# EasyEDAProject.net
KiCad netlist of a schematic drawn in EasyEDA Pro
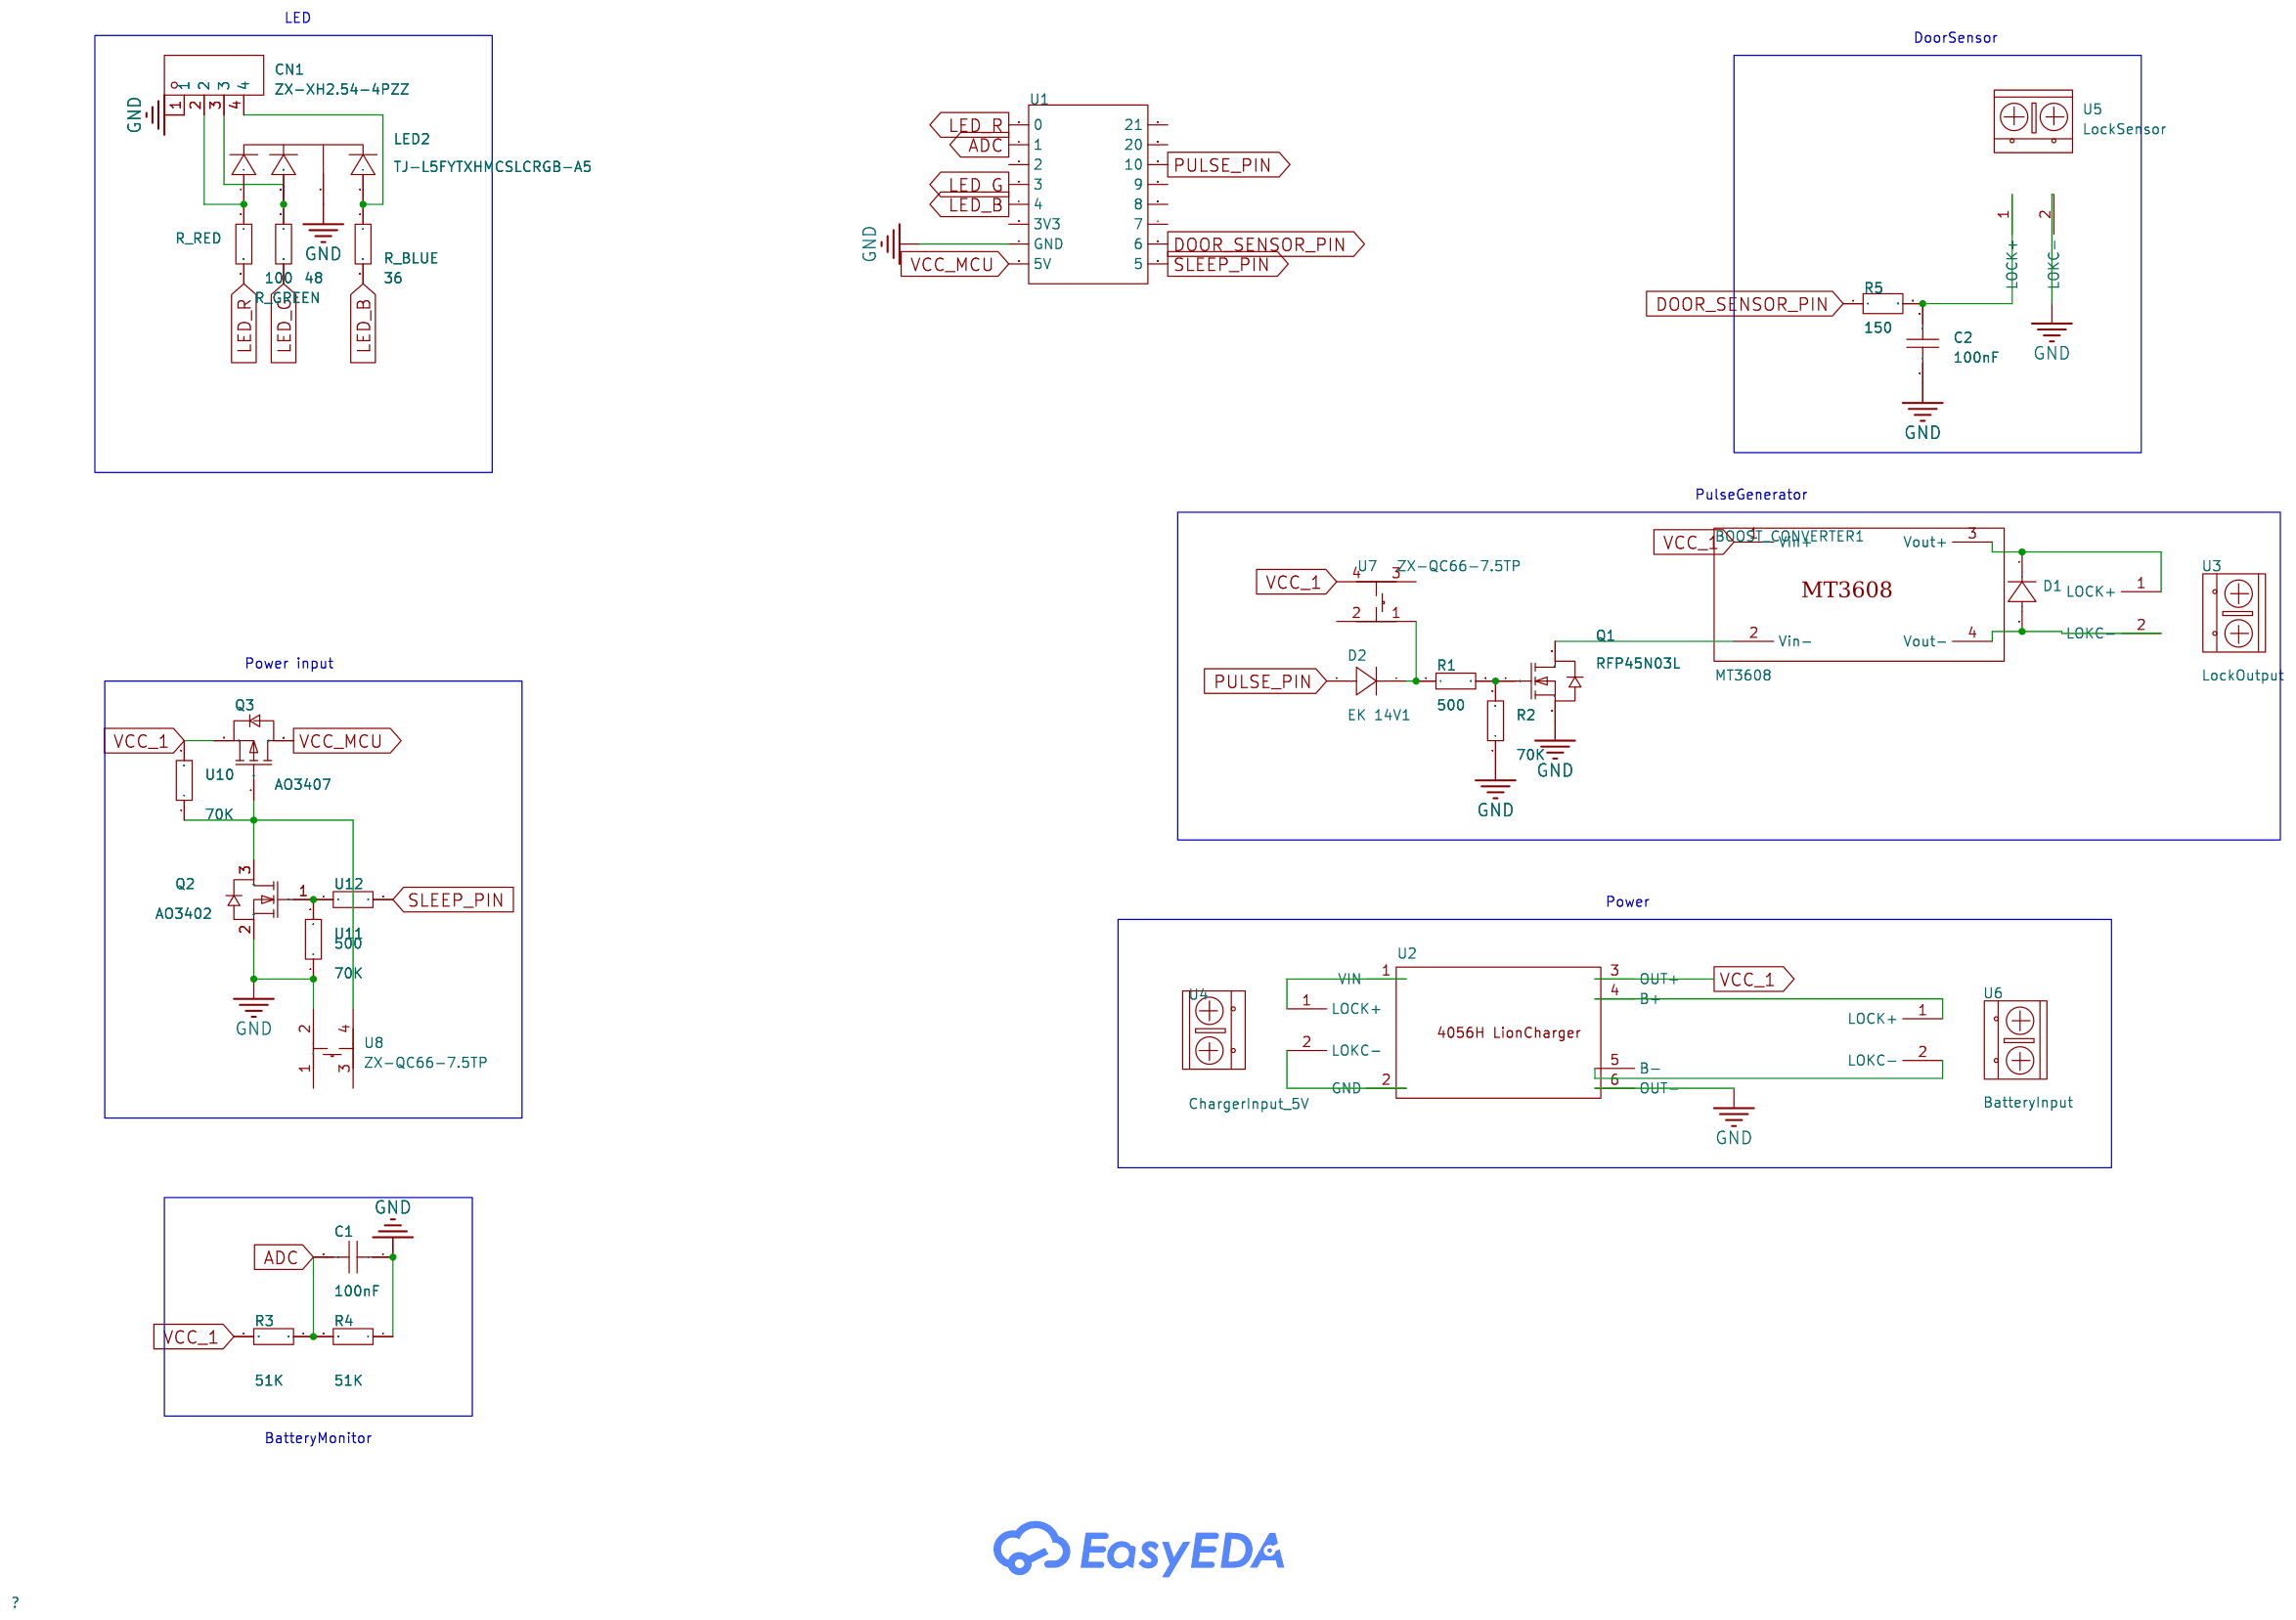
[diagram p0: schematic sheet]

(export (version "E")
  (design (tool "Eeschema 10.0.6"))
  (components
    (comp (ref "BOOST_CONVERTER1")
      (value "MT3608")
      (footprint "easyedapro:MT3608 BOOST")
      (libsource (lib "easyedapro") (part "MT3608"))
    )
    (comp (ref "C1")
      (value "100nF")
      (footprint "easyedapro:C0603")
      (libsource (lib "easyedapro") (part "CAP"))
    )
    (comp (ref "C2")
      (value "100nF")
      (footprint "easyedapro:CAP-TH_L5.0-W2.5-P5.00-D1.0")
      (fields
        (field (name "Manufacturer Part") "CC1H104MC1FD3F6C10MF")
        (field (name "Manufacturer") "Dersonic(德尔创)")
      )
      (libsource (lib "easyedapro") (part "CC1H104MC1FD3F6C10MF"))
    )
    (comp (ref "CN1")
      (value "ZX-XH2.54-4PZZ")
      (footprint "easyedapro:CONN-TH_4P-P2.50_4PIN")
      (fields (field (name "Manufacturer") "Megastar(兆星)"))
      (libsource (lib "easyedapro") (part "ZX-XH2.54-4PZZ"))
    )
    (comp (ref "D1")
      (value "~")
      (footprint "easyedapro:SMA_L4.4-W2.8-LS5.4-RD")
      (libsource (lib "easyedapro") (part "D_1N4007"))
    )
    (comp (ref "D2")
      (value "EK 14V1")
      (footprint "easyedapro:SMA_L4.4-W2.8-LS5.4-RD")
      (fields (field (name "Manufacturer") "SANKEN(三垦)"))
      (libsource (lib "easyedapro") (part "D_1N4007"))
    )
    (comp (ref "LED2")
      (value "TJ-L5FYTXHMCSLCRGB-A5")
      (footprint "easyedapro:LED-TH_4P-BD5.8-P1.30")
      (fields (field (name "Manufacturer") "TOGIALED(统佳)"))
      (libsource (lib "easyedapro") (part "TJ-L5FYTXHMCSLCRGB-A5"))
    )
    (comp (ref "Q1")
      (value "RFP45N03L")
      (footprint "easyedapro:TO-220-3_L9.9-W4.5-P2.54-L")
      (fields (field (name "Manufacturer") "HARRIS(哈利斯)"))
      (libsource (lib "easyedapro") (part "RFP45N03L"))
    )
    (comp (ref "Q2")
      (value "AO3402")
      (footprint "easyedapro:SOT-23_L2.9-W1.3-P1.90-LS2.4-BR")
      (fields (field (name "Manufacturer") "GOODWORK(固得沃克)"))
      (libsource (lib "easyedapro") (part "AO3402_C2938369"))
    )
    (comp (ref "Q3")
      (value "AO3407")
      (footprint "easyedapro:SOT-23-3_L2.9-W1.3-P1.90-LS2.4-BR")
      (fields (field (name "Manufacturer") "YONGYUTAI(永裕泰)"))
      (libsource (lib "easyedapro") (part "AO3407_C6562206"))
    )
    (comp (ref "R1")
      (value "500")
      (footprint "easyedapro:R_AXIAL-0.5")
      (libsource (lib "easyedapro") (part "Res"))
    )
    (comp (ref "R2")
      (value "70K")
      (footprint "easyedapro:R_AXIAL-0.5")
      (libsource (lib "easyedapro") (part "Res"))
    )
    (comp (ref "R3")
      (value "51K")
      (footprint "easyedapro:R_AXIAL-0.5")
      (libsource (lib "easyedapro") (part "Res"))
    )
    (comp (ref "R4")
      (value "51K")
      (footprint "easyedapro:R_AXIAL-0.5")
      (libsource (lib "easyedapro") (part "Res"))
    )
    (comp (ref "R5")
      (value "150")
      (footprint "easyedapro:RES-TH_BD2.3-L6.5-P10.50-D0.5")
      (fields (field (name "Manufacturer Part") "MF1/4W-1KΩ±1%T52") (field (name "Manufacturer") "华星机电"))
      (libsource (lib "easyedapro") (part "MF1/4W-1KΩ±1%T52"))
    )
    (comp (ref "R_BLUE")
      (value "36")
      (footprint "easyedapro:R_AXIAL-0.5")
      (libsource (lib "easyedapro") (part "Res"))
    )
    (comp (ref "R_GREEN")
      (value "48")
      (footprint "easyedapro:R_AXIAL-0.5")
      (libsource (lib "easyedapro") (part "Res"))
    )
    (comp (ref "R_RED")
      (value "100")
      (footprint "easyedapro:R_AXIAL-0.5")
      (libsource (lib "easyedapro") (part "Res"))
    )
    (comp (ref "U1")
      (value "~")
      (footprint "easyedapro:ESP32-C3 SuperMini")
      (libsource (lib "easyedapro") (part "ESP32-C3 SuperMini"))
    )
    (comp (ref "U2")
      (value "~")
      (footprint "easyedapro:LionCharger")
      (libsource (lib "easyedapro") (part "Lio-Charger"))
    )
    (comp (ref "U3")
      (value "LockOutput")
      (footprint "easyedapro:TerminalBlock:TerminalBlock_bornier-2_P5.08mm")
      (libsource (lib "easyedapro") (part "2pin Terminal"))
    )
    (comp (ref "U4")
      (value "ChargerInput_5V")
      (footprint "easyedapro:TerminalBlock:TerminalBlock_bornier-2_P5.08mm")
      (libsource (lib "easyedapro") (part "2pin Terminal"))
    )
    (comp (ref "U5")
      (value "LockSensor")
      (footprint "easyedapro:TerminalBlock:TerminalBlock_bornier-2_P5.08mm")
      (libsource (lib "easyedapro") (part "2pin Terminal"))
    )
    (comp (ref "U6")
      (value "BatteryInput")
      (footprint "easyedapro:TerminalBlock:TerminalBlock_bornier-2_P5.08mm")
      (libsource (lib "easyedapro") (part "2pin Terminal"))
    )
    (comp (ref "U7")
      (value "ZX-QC66-7.5TP")
      (footprint "easyedapro:KEY-SMD_4P-L6.0-W6.0-P4.50-LS8.6")
      (fields (field (name "Manufacturer") "Megastar(兆星)"))
      (libsource (lib "easyedapro") (part "ZX-QC66-7.5TP"))
    )
    (comp (ref "U8")
      (value "ZX-QC66-7.5TP")
      (footprint "easyedapro:KEY-SMD_4P-L6.0-W6.0-P4.50-LS8.6")
      (fields (field (name "Manufacturer") "Megastar(兆星)"))
      (libsource (lib "easyedapro") (part "ZX-QC66-7.5TP"))
    )
    (comp (ref "U10")
      (value "70K")
      (footprint "easyedapro:R_AXIAL-0.5")
      (libsource (lib "easyedapro") (part "Res"))
    )
    (comp (ref "U11")
      (value "70K")
      (footprint "easyedapro:R_AXIAL-0.5")
      (libsource (lib "easyedapro") (part "Res"))
    )
    (comp (ref "U12")
      (value "500")
      (footprint "easyedapro:R_AXIAL-0.5")
      (libsource (lib "easyedapro") (part "Res"))
    )
  )
  (nets
    (net (code "1") (name "ADC") (class "Default")
      (node (ref "C1") (pin "2") (pinfunction "2_2") (pintype "input"))
      (node (ref "R3") (pin "1") (pinfunction "1_1") (pintype "input"))
      (node (ref "R4") (pin "2") (pinfunction "2_2") (pintype "input"))
      (node (ref "U1") (pin "1") (pinfunction "1_1") (pintype "input"))
    )
    (net (code "2") (name "DOOR_SENSOR_PIN") (class "Default")
      (node (ref "R5") (pin "1") (pinfunction "1_1") (pintype "unspecified"))
      (node (ref "U1") (pin "6") (pinfunction "6_6") (pintype "input"))
    )
    (net (code "3") (name "GND") (class "Default")
      (node (ref "C1") (pin "1") (pinfunction "1_1") (pintype "input"))
      (node (ref "C2") (pin "1") (pinfunction "1_1") (pintype "unspecified"))
      (node (ref "CN1") (pin "1") (pinfunction "1_1") (pintype "unspecified"))
      (node (ref "LED2") (pin "2") (pinfunction "-_2") (pintype "unspecified"))
      (node (ref "Q1") (pin "3") (pinfunction "S_3") (pintype "unspecified"))
      (node (ref "Q2") (pin "2") (pinfunction "S_2") (pintype "unspecified"))
      (node (ref "R2") (pin "1") (pinfunction "1_1") (pintype "input"))
      (node (ref "R4") (pin "1") (pinfunction "1_1") (pintype "input"))
      (node (ref "U1") (pin "14") (pinfunction "GND_14") (pintype "input"))
      (node (ref "U11") (pin "1") (pinfunction "1_1") (pintype "input"))
      (node (ref "U2") (pin "6") (pinfunction "OUT-_6") (pintype "output"))
      (node (ref "U5") (pin "2") (pinfunction "LOKC-_2") (pintype "input"))
      (node (ref "U8") (pin "2") (pinfunction "2_2") (pintype "unspecified"))
    )
    (net (code "4") (name "LED_B") (class "Default")
      (node (ref "R_BLUE") (pin "2") (pinfunction "2_2") (pintype "input"))
      (node (ref "U1") (pin "4") (pinfunction "4_4") (pintype "input"))
    )
    (net (code "5") (name "LED_G") (class "Default")
      (node (ref "R_GREEN") (pin "2") (pinfunction "2_2") (pintype "input"))
      (node (ref "U1") (pin "3") (pinfunction "3_3") (pintype "input"))
    )
    (net (code "6") (name "LED_R") (class "Default")
      (node (ref "R_RED") (pin "2") (pinfunction "2_2") (pintype "input"))
      (node (ref "U1") (pin "0") (pinfunction "0_0") (pintype "input"))
    )
    (net (code "7") (name "Net-(BOOST_CONVERTER1-Vin-)") (class "Default")
      (node (ref "BOOST_CONVERTER1") (pin "2") (pinfunction "Vin-_2") (pintype "input"))
      (node (ref "Q1") (pin "2") (pinfunction "D_2") (pintype "unspecified"))
    )
    (net (code "8") (name "Net-(BOOST_CONVERTER1-Vout+)") (class "Default")
      (node (ref "BOOST_CONVERTER1") (pin "3") (pinfunction "Vout+_3") (pintype "input"))
      (node (ref "D1") (pin "1") (pinfunction "K_1") (pintype "input"))
      (node (ref "U3") (pin "1") (pinfunction "LOCK+_1") (pintype "input"))
    )
    (net (code "9") (name "Net-(BOOST_CONVERTER1-Vout-)") (class "Default")
      (node (ref "BOOST_CONVERTER1") (pin "4") (pinfunction "Vout-_4") (pintype "input"))
      (node (ref "D1") (pin "2") (pinfunction "A_2") (pintype "input"))
      (node (ref "U3") (pin "2") (pinfunction "LOKC-_2") (pintype "input"))
    )
    (net (code "10") (name "Net-(CN1-Pad2)") (class "Default")
      (node (ref "CN1") (pin "2") (pinfunction "2_2") (pintype "unspecified"))
      (node (ref "LED2") (pin "4") (pinfunction "4_4") (pintype "unspecified"))
      (node (ref "R_RED") (pin "1") (pinfunction "1_1") (pintype "input"))
    )
    (net (code "11") (name "Net-(CN1-Pad3)") (class "Default")
      (node (ref "CN1") (pin "3") (pinfunction "3_3") (pintype "unspecified"))
      (node (ref "LED2") (pin "3") (pinfunction "3_3") (pintype "unspecified"))
      (node (ref "R_GREEN") (pin "1") (pinfunction "1_1") (pintype "input"))
    )
    (net (code "12") (name "Net-(CN1-Pad4)") (class "Default")
      (node (ref "CN1") (pin "4") (pinfunction "4_4") (pintype "unspecified"))
      (node (ref "LED2") (pin "1") (pinfunction "1_1") (pintype "unspecified"))
      (node (ref "R_BLUE") (pin "1") (pinfunction "1_1") (pintype "input"))
    )
    (net (code "13") (name "Net-(D2-K)") (class "Default")
      (node (ref "D2") (pin "1") (pinfunction "K_1") (pintype "input"))
      (node (ref "R1") (pin "1") (pinfunction "1_1") (pintype "input"))
      (node (ref "U7") (pin "1") (pinfunction "1_1") (pintype "unspecified"))
    )
    (net (code "14") (name "Net-(Q1-G)") (class "Default")
      (node (ref "Q1") (pin "1") (pinfunction "G_1") (pintype "unspecified"))
      (node (ref "R1") (pin "2") (pinfunction "2_2") (pintype "input"))
      (node (ref "R2") (pin "2") (pinfunction "2_2") (pintype "input"))
    )
    (net (code "15") (name "Net-(Q2-D)") (class "Default")
      (node (ref "Q2") (pin "3") (pinfunction "D_3") (pintype "unspecified"))
      (node (ref "Q3") (pin "1") (pinfunction "G_1") (pintype "unspecified"))
      (node (ref "U10") (pin "1") (pinfunction "1_1") (pintype "input"))
      (node (ref "U8") (pin "4") (pinfunction "4_4") (pintype "unspecified"))
    )
    (net (code "16") (name "Net-(Q2-G)") (class "Default")
      (node (ref "Q2") (pin "1") (pinfunction "G_1") (pintype "unspecified"))
      (node (ref "U11") (pin "2") (pinfunction "2_2") (pintype "input"))
      (node (ref "U12") (pin "1") (pinfunction "1_1") (pintype "input"))
    )
    (net (code "17") (name "Net-(U2-B+)") (class "Default")
      (node (ref "U2") (pin "4") (pinfunction "B+_4") (pintype "input"))
      (node (ref "U6") (pin "1") (pinfunction "LOCK+_1") (pintype "input"))
    )
    (net (code "18") (name "Net-(U2-B-)") (class "Default")
      (node (ref "U2") (pin "5") (pinfunction "B-_5") (pintype "input"))
      (node (ref "U6") (pin "2") (pinfunction "LOKC-_2") (pintype "input"))
    )
    (net (code "19") (name "Net-(U2-GND)") (class "Default")
      (node (ref "U2") (pin "2") (pinfunction "GND_2") (pintype "input"))
      (node (ref "U4") (pin "2") (pinfunction "LOKC-_2") (pintype "input"))
    )
    (net (code "20") (name "Net-(U2-VIN)") (class "Default")
      (node (ref "U2") (pin "1") (pinfunction "VIN_1") (pintype "input"))
      (node (ref "U4") (pin "1") (pinfunction "LOCK+_1") (pintype "input"))
    )
    (net (code "21") (name "Net-(U5-LOCK+)") (class "Default")
      (node (ref "C2") (pin "2") (pinfunction "2_2") (pintype "unspecified"))
      (node (ref "R5") (pin "2") (pinfunction "2_2") (pintype "unspecified"))
      (node (ref "U5") (pin "1") (pinfunction "LOCK+_1") (pintype "input"))
    )
    (net (code "22") (name "PULSE_PIN") (class "Default")
      (node (ref "D2") (pin "2") (pinfunction "A_2") (pintype "input"))
      (node (ref "U1") (pin "10") (pinfunction "10_10") (pintype "input"))
    )
    (net (code "23") (name "SLEEP_PIN") (class "Default")
      (node (ref "U1") (pin "5") (pinfunction "5_5") (pintype "input"))
      (node (ref "U12") (pin "2") (pinfunction "2_2") (pintype "input"))
    )
    (net (code "24") (name "VCC_1") (class "Default")
      (node (ref "BOOST_CONVERTER1") (pin "1") (pinfunction "Vin+_1") (pintype "input"))
      (node (ref "Q3") (pin "2") (pinfunction "S_2") (pintype "unspecified"))
      (node (ref "R3") (pin "2") (pinfunction "2_2") (pintype "input"))
      (node (ref "U10") (pin "2") (pinfunction "2_2") (pintype "input"))
      (node (ref "U2") (pin "3") (pinfunction "OUT+_3") (pintype "output"))
      (node (ref "U7") (pin "4") (pinfunction "4_4") (pintype "unspecified"))
    )
    (net (code "25") (name "VCC_MCU") (class "Default")
      (node (ref "Q3") (pin "3") (pinfunction "D_3") (pintype "unspecified"))
      (node (ref "U1") (pin "15") (pinfunction "5V_15") (pintype "input"))
    )
    (net (code "26") (name "unconnected-(U1-3V3-Pad13)") (class "Default")
      (node (ref "U1") (pin "13") (pinfunction "3V3_13") (pintype "input"))
    )
    (net (code "27") (name "unconnected-(U1-Pad2)") (class "Default")
      (node (ref "U1") (pin "2") (pinfunction "2_2") (pintype "input"))
    )
    (net (code "28") (name "unconnected-(U1-Pad7)") (class "Default")
      (node (ref "U1") (pin "7") (pinfunction "7_7") (pintype "input"))
    )
    (net (code "29") (name "unconnected-(U1-Pad8)") (class "Default")
      (node (ref "U1") (pin "8") (pinfunction "8_8") (pintype "input"))
    )
    (net (code "30") (name "unconnected-(U1-Pad9)") (class "Default")
      (node (ref "U1") (pin "9") (pinfunction "9_9") (pintype "input"))
    )
    (net (code "31") (name "unconnected-(U1-Pad20)") (class "Default")
      (node (ref "U1") (pin "20") (pinfunction "20_20") (pintype "input"))
    )
    (net (code "32") (name "unconnected-(U1-Pad21)") (class "Default")
      (node (ref "U1") (pin "21") (pinfunction "21_21") (pintype "input"))
    )
    (net (code "33") (name "unconnected-(U7-Pad2)") (class "Default")
      (node (ref "U7") (pin "2") (pinfunction "2_2") (pintype "unspecified"))
    )
    (net (code "34") (name "unconnected-(U7-Pad3)") (class "Default")
      (node (ref "U7") (pin "3") (pinfunction "3_3") (pintype "unspecified"))
    )
    (net (code "35") (name "unconnected-(U8-Pad1)") (class "Default")
      (node (ref "U8") (pin "1") (pinfunction "1_1") (pintype "unspecified"))
    )
    (net (code "36") (name "unconnected-(U8-Pad3)") (class "Default")
      (node (ref "U8") (pin "3") (pinfunction "3_3") (pintype "unspecified"))
    )
  )
)
